# power.net
KiCad netlist of a schematic drawn in Altium Designer
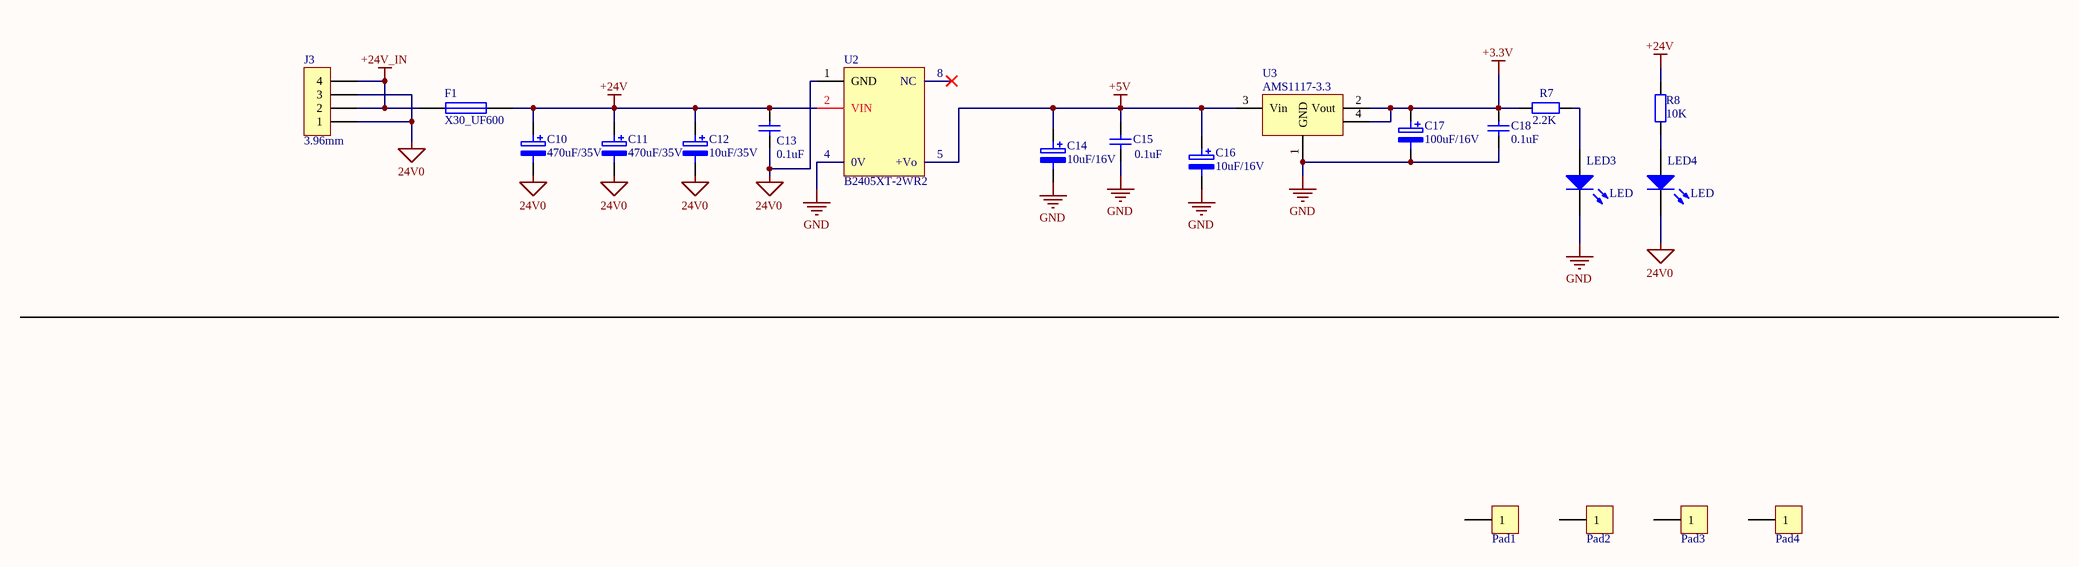
[diagram p0: power.SchDoc]

(export (version "E")
  (design (tool "Eeschema 10.0.6"))
  (components
    (comp (ref "C10")
      (value "470uF/35V")
      (footprint "CE/10MM")
      (description "Electrolytic Capacitor")
      (libsource (lib "Mylib") (part "ELECTRO2"))
    )
    (comp (ref "C11")
      (value "470uF/35V")
      (footprint "CE/10MM")
      (description "Electrolytic Capacitor")
      (libsource (lib "Mylib") (part "ELECTRO2"))
    )
    (comp (ref "C12")
      (value "10uF/35V")
      (footprint "TC6032_C")
      (description "Electrolytic Capacitor")
      (libsource (lib "Mylib") (part "ELECTRO2"))
    )
    (comp (ref "C13")
      (value "0.1uF")
      (footprint "0805_CAP")
      (description "Capacitor")
      (fields (field (name "PUBLISHER") "Altium Limited"))
      (libsource (lib "Miscellaneous Devices") (part "Cap"))
    )
    (comp (ref "C14")
      (value "10uF/16V")
      (footprint "CASE-A_3216")
      (description "Electrolytic Capacitor")
      (libsource (lib "Mylib") (part "ELECTRO2"))
    )
    (comp (ref "C15")
      (value "0.1uF")
      (footprint "0805_CAP")
      (description "Capacitor")
      (fields (field (name "PUBLISHER") "Altium Limited"))
      (libsource (lib "Miscellaneous Devices") (part "Cap"))
    )
    (comp (ref "C16")
      (value "10uF/16V")
      (footprint "CASE-A_3216")
      (description "Electrolytic Capacitor")
      (libsource (lib "Mylib") (part "ELECTRO2"))
    )
    (comp (ref "C17")
      (value "100uF/16V")
      (footprint "TC6032_C")
      (description "Electrolytic Capacitor")
      (libsource (lib "Mylib") (part "ELECTRO2"))
    )
    (comp (ref "C18")
      (value "0.1uF")
      (footprint "0805_CAP")
      (description "Capacitor")
      (fields (field (name "PUBLISHER") "Altium Limited"))
      (libsource (lib "Miscellaneous Devices") (part "Cap"))
    )
    (comp (ref "F1")
      (value "X30_UF600")
      (footprint "X30UF600")
      (description "Fuse")
      (fields (field (name "PUBLISHER") "Altium Limited"))
      (libsource (lib "Miscellaneous Devices") (part "Fuse 1"))
    )
    (comp (ref "J3")
      (value "3.96mm")
      (footprint "VH3.96_4P")
      (description "Connector")
      (libsource (lib "MyLibrary") (part "CON4"))
    )
    (comp (ref "LED3")
      (value "LED")
      (footprint "0805-LED-G")
      (description "Typical RED, GREEN, YELLOW, AMBER GaAs LED")
      (fields (field (name "PUBLISHER") "Altium Limited"))
      (libsource (lib "Miscellaneous Devices") (part "LED2"))
    )
    (comp (ref "LED4")
      (value "LED")
      (footprint "0805-LED-G")
      (description "Typical RED, GREEN, YELLOW, AMBER GaAs LED")
      (fields (field (name "PUBLISHER") "Altium Limited"))
      (libsource (lib "Miscellaneous Devices") (part "LED2"))
    )
    (comp (ref "Pad1")
      (value "Pad")
      (footprint "pad35")
      (libsource (lib "myIntegrated_Library1") (part "Pad"))
    )
    (comp (ref "Pad2")
      (value "Pad")
      (footprint "pad35")
      (libsource (lib "myIntegrated_Library1") (part "Pad"))
    )
    (comp (ref "Pad3")
      (value "Pad")
      (footprint "pad35")
      (libsource (lib "myIntegrated_Library1") (part "Pad"))
    )
    (comp (ref "Pad4")
      (value "Pad")
      (footprint "pad35")
      (libsource (lib "myIntegrated_Library1") (part "Pad"))
    )
    (comp (ref "R7")
      (value "2.2K")
      (footprint "0805_RES")
      (description "Resistor")
      (fields (field (name "PUBLISHER") "Altium Limited"))
      (libsource (lib "") (part "Res2_1"))
    )
    (comp (ref "R8")
      (value "10K")
      (footprint "0805_RES")
      (description "Resistor")
      (fields (field (name "PUBLISHER") "Altium Limited"))
      (libsource (lib "Miscellaneous Devices") (part "Res2"))
    )
    (comp (ref "U2")
      (value "B2405XT-2WR2")
      (footprint "B2405XT-2WR2")
      (libsource (lib "MyLibrary") (part "B2405XT-2WR2"))
    )
    (comp (ref "U3")
      (value "AMS1117-3.3")
      (footprint "SOT223_3")
      (libsource (lib "货架电子标签元件库") (part "AMS1117-5"))
    )
  )
  (nets
    (net (code "1") (name "+3.3V") (class "Default")
      (node (ref "C17") (pin "1") (pinfunction "1_1") (pintype "passive"))
      (node (ref "C18") (pin "2") (pinfunction "2_2") (pintype "passive"))
      (node (ref "R7") (pin "2") (pinfunction "2_2") (pintype "passive"))
      (node (ref "U3") (pin "2") (pinfunction "Vout_2") (pintype "passive"))
      (node (ref "U3") (pin "4") (pintype "passive"))
    )
    (net (code "2") (name "+5V") (class "Default")
      (node (ref "C14") (pin "1") (pinfunction "1_1") (pintype "passive"))
      (node (ref "C15") (pin "2") (pinfunction "2_2") (pintype "passive"))
      (node (ref "C16") (pin "1") (pinfunction "1_1") (pintype "passive"))
      (node (ref "U2") (pin "5") (pinfunction "+Vo_5") (pintype "passive"))
      (node (ref "U3") (pin "3") (pinfunction "Vin_3") (pintype "passive"))
    )
    (net (code "3") (name "+24V") (class "Default")
      (node (ref "C10") (pin "1") (pinfunction "1_1") (pintype "passive"))
      (node (ref "C11") (pin "1") (pinfunction "1_1") (pintype "passive"))
      (node (ref "C12") (pin "1") (pinfunction "1_1") (pintype "passive"))
      (node (ref "C13") (pin "2") (pinfunction "2_2") (pintype "passive"))
      (node (ref "F1") (pin "2") (pinfunction "2_2") (pintype "passive"))
      (node (ref "R8") (pin "2") (pinfunction "2_2") (pintype "passive"))
      (node (ref "U2") (pin "2") (pinfunction "VIN_2") (pintype "passive"))
    )
    (net (code "4") (name "+24V_IN") (class "Default")
      (node (ref "F1") (pin "1") (pinfunction "1_1") (pintype "passive"))
      (node (ref "J3") (pin "2") (pinfunction "2_2") (pintype "passive"))
      (node (ref "J3") (pin "4") (pinfunction "4_4") (pintype "passive"))
    )
    (net (code "5") (name "24V0") (class "Default")
      (node (ref "C10") (pin "2") (pinfunction "2_2") (pintype "passive"))
      (node (ref "C11") (pin "2") (pinfunction "2_2") (pintype "passive"))
      (node (ref "C12") (pin "2") (pinfunction "2_2") (pintype "passive"))
      (node (ref "C13") (pin "1") (pinfunction "1_1") (pintype "passive"))
      (node (ref "J3") (pin "1") (pinfunction "1_1") (pintype "passive"))
      (node (ref "J3") (pin "3") (pinfunction "3_3") (pintype "passive"))
      (node (ref "LED4") (pin "2") (pinfunction "K_2") (pintype "passive"))
      (node (ref "U2") (pin "1") (pinfunction "GND_1") (pintype "passive"))
    )
    (net (code "6") (name "GND") (class "Default")
      (node (ref "C14") (pin "2") (pinfunction "2_2") (pintype "passive"))
      (node (ref "C15") (pin "1") (pinfunction "1_1") (pintype "passive"))
      (node (ref "C16") (pin "2") (pinfunction "2_2") (pintype "passive"))
      (node (ref "C17") (pin "2") (pinfunction "2_2") (pintype "passive"))
      (node (ref "C18") (pin "1") (pinfunction "1_1") (pintype "passive"))
      (node (ref "LED3") (pin "2") (pinfunction "K_2") (pintype "passive"))
      (node (ref "U2") (pin "4") (pinfunction "0V_4") (pintype "passive"))
      (node (ref "U3") (pin "1") (pinfunction "GND_1") (pintype "passive"))
    )
    (net (code "7") (name "Net-(LED3-A)") (class "Default")
      (node (ref "LED3") (pin "1") (pinfunction "A_1") (pintype "passive"))
      (node (ref "R7") (pin "1") (pinfunction "1_1") (pintype "passive"))
    )
    (net (code "8") (name "Net-(LED4-A)") (class "Default")
      (node (ref "LED4") (pin "1") (pinfunction "A_1") (pintype "passive"))
      (node (ref "R8") (pin "1") (pinfunction "1_1") (pintype "passive"))
    )
    (net (code "9") (name "unconnected-(Pad1-Pad1)") (class "Default")
      (node (ref "Pad1") (pin "1") (pinfunction "1_1") (pintype "passive"))
    )
    (net (code "10") (name "unconnected-(Pad2-Pad1)") (class "Default")
      (node (ref "Pad2") (pin "1") (pinfunction "1_1") (pintype "passive"))
    )
    (net (code "11") (name "unconnected-(Pad3-Pad1)") (class "Default")
      (node (ref "Pad3") (pin "1") (pinfunction "1_1") (pintype "passive"))
    )
    (net (code "12") (name "unconnected-(Pad4-Pad1)") (class "Default")
      (node (ref "Pad4") (pin "1") (pinfunction "1_1") (pintype "passive"))
    )
    (net (code "13") (name "unconnected-(U2-NC-Pad8)") (class "Default")
      (node (ref "U2") (pin "8") (pinfunction "NC_8") (pintype "passive+no_connect"))
    )
  )
)
